# norbi_lm_mem.net
KiCad netlist of a schematic drawn in Altium Designer
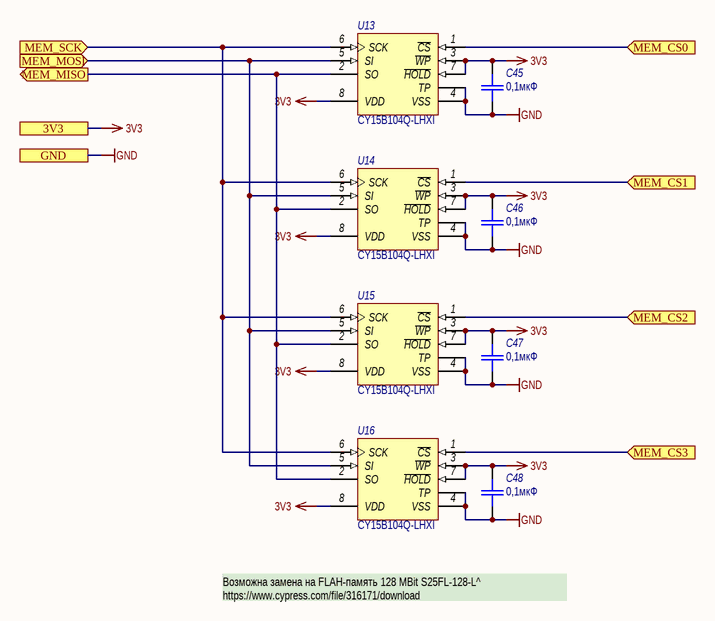
[diagram p0: norbi_lm_mem.SchDoc]

(export (version "E")
  (design (tool "Eeschema 10.0.6"))
  (components
    (comp (ref "C45")
      (value "0,1мкФ")
      (footprint "CR-0603")
      (description "Конденсатор для поверхностного монтажа")
      (libsource (lib "my_passive") (part "C_smd"))
    )
    (comp (ref "C46")
      (value "0,1мкФ")
      (footprint "CR-0603")
      (description "Конденсатор для поверхностного монтажа")
      (libsource (lib "my_passive") (part "C_smd"))
    )
    (comp (ref "C47")
      (value "0,1мкФ")
      (footprint "CR-0603")
      (description "Конденсатор для поверхностного монтажа")
      (libsource (lib "my_passive") (part "C_smd"))
    )
    (comp (ref "C48")
      (value "0,1мкФ")
      (footprint "CR-0603")
      (description "Конденсатор для поверхностного монтажа")
      (libsource (lib "my_passive") (part "C_smd"))
    )
    (comp (ref "U13")
      (value "FM25V20")
      (footprint "TDFN-8")
      (description "2Mb Serial 3V FRAM Memory")
      (fields (field (name "НАИМЕНОВАНИЕ") "CY15B104Q-LHXI"))
      (libsource (lib "my_memory") (part "FM25V"))
    )
    (comp (ref "U14")
      (value "FM25V20")
      (footprint "TDFN-8")
      (description "2Mb Serial 3V FRAM Memory")
      (fields (field (name "НАИМЕНОВАНИЕ") "CY15B104Q-LHXI"))
      (libsource (lib "my_memory") (part "FM25V"))
    )
    (comp (ref "U15")
      (value "FM25V20")
      (footprint "TDFN-8")
      (description "2Mb Serial 3V FRAM Memory")
      (fields (field (name "НАИМЕНОВАНИЕ") "CY15B104Q-LHXI"))
      (libsource (lib "my_memory") (part "FM25V"))
    )
    (comp (ref "U16")
      (value "FM25V20")
      (footprint "TDFN-8")
      (description "2Mb Serial 3V FRAM Memory")
      (fields (field (name "НАИМЕНОВАНИЕ") "CY15B104Q-LHXI"))
      (libsource (lib "my_memory") (part "FM25V"))
    )
  )
  (nets
    (net (code "1") (name "/MEM_CS0") (class "Default")
      (node (ref "U13") (pin "1") (pinfunction "~{CS}_1") (pintype "input"))
    )
    (net (code "2") (name "/MEM_CS1") (class "Default")
      (node (ref "U14") (pin "1") (pinfunction "~{CS}_1") (pintype "input"))
    )
    (net (code "3") (name "/MEM_CS2") (class "Default")
      (node (ref "U15") (pin "1") (pinfunction "~{CS}_1") (pintype "input"))
    )
    (net (code "4") (name "/MEM_CS3") (class "Default")
      (node (ref "U16") (pin "1") (pinfunction "~{CS}_1") (pintype "input"))
    )
    (net (code "5") (name "/MEM_MISO") (class "Default")
      (node (ref "U13") (pin "2") (pinfunction "SO_2") (pintype "tri_state"))
      (node (ref "U14") (pin "2") (pinfunction "SO_2") (pintype "tri_state"))
      (node (ref "U15") (pin "2") (pinfunction "SO_2") (pintype "tri_state"))
      (node (ref "U16") (pin "2") (pinfunction "SO_2") (pintype "tri_state"))
    )
    (net (code "6") (name "/MEM_MOSI") (class "Default")
      (node (ref "U13") (pin "5") (pinfunction "SI_5") (pintype "input"))
      (node (ref "U14") (pin "5") (pinfunction "SI_5") (pintype "input"))
      (node (ref "U15") (pin "5") (pinfunction "SI_5") (pintype "input"))
      (node (ref "U16") (pin "5") (pinfunction "SI_5") (pintype "input"))
    )
    (net (code "7") (name "/MEM_SCK") (class "Default")
      (node (ref "U13") (pin "6") (pinfunction "SCK_6") (pintype "input"))
      (node (ref "U14") (pin "6") (pinfunction "SCK_6") (pintype "input"))
      (node (ref "U15") (pin "6") (pinfunction "SCK_6") (pintype "input"))
      (node (ref "U16") (pin "6") (pinfunction "SCK_6") (pintype "input"))
    )
    (net (code "8") (name "3V3") (class "Default")
      (node (ref "C45") (pin "2") (pinfunction "2_2") (pintype "passive"))
      (node (ref "C46") (pin "2") (pinfunction "2_2") (pintype "passive"))
      (node (ref "C47") (pin "2") (pinfunction "2_2") (pintype "passive"))
      (node (ref "C48") (pin "2") (pinfunction "2_2") (pintype "passive"))
      (node (ref "U13") (pin "3") (pinfunction "~{WP}_3") (pintype "input"))
      (node (ref "U13") (pin "7") (pinfunction "~{HOLD}_7") (pintype "input"))
      (node (ref "U13") (pin "8") (pinfunction "VDD_8") (pintype "power_in"))
      (node (ref "U14") (pin "3") (pinfunction "~{WP}_3") (pintype "input"))
      (node (ref "U14") (pin "7") (pinfunction "~{HOLD}_7") (pintype "input"))
      (node (ref "U14") (pin "8") (pinfunction "VDD_8") (pintype "power_in"))
      (node (ref "U15") (pin "3") (pinfunction "~{WP}_3") (pintype "input"))
      (node (ref "U15") (pin "7") (pinfunction "~{HOLD}_7") (pintype "input"))
      (node (ref "U15") (pin "8") (pinfunction "VDD_8") (pintype "power_in"))
      (node (ref "U16") (pin "3") (pinfunction "~{WP}_3") (pintype "input"))
      (node (ref "U16") (pin "7") (pinfunction "~{HOLD}_7") (pintype "input"))
      (node (ref "U16") (pin "8") (pinfunction "VDD_8") (pintype "power_in"))
    )
    (net (code "9") (name "GND") (class "Default")
      (node (ref "C45") (pin "1") (pinfunction "1_1") (pintype "passive"))
      (node (ref "C46") (pin "1") (pinfunction "1_1") (pintype "passive"))
      (node (ref "C47") (pin "1") (pinfunction "1_1") (pintype "passive"))
      (node (ref "C48") (pin "1") (pinfunction "1_1") (pintype "passive"))
      (node (ref "U13") (pin "4") (pinfunction "VSS_4") (pintype "power_in"))
      (node (ref "U13") (pin "TP") (pinfunction "TP_TP") (pintype "power_in"))
      (node (ref "U14") (pin "4") (pinfunction "VSS_4") (pintype "power_in"))
      (node (ref "U14") (pin "TP") (pinfunction "TP_TP") (pintype "power_in"))
      (node (ref "U15") (pin "4") (pinfunction "VSS_4") (pintype "power_in"))
      (node (ref "U15") (pin "TP") (pinfunction "TP_TP") (pintype "power_in"))
      (node (ref "U16") (pin "4") (pinfunction "VSS_4") (pintype "power_in"))
      (node (ref "U16") (pin "TP") (pinfunction "TP_TP") (pintype "power_in"))
    )
  )
)
